# nse5310-module-stm32.net
KiCad netlist of a schematic drawn in Altium Designer
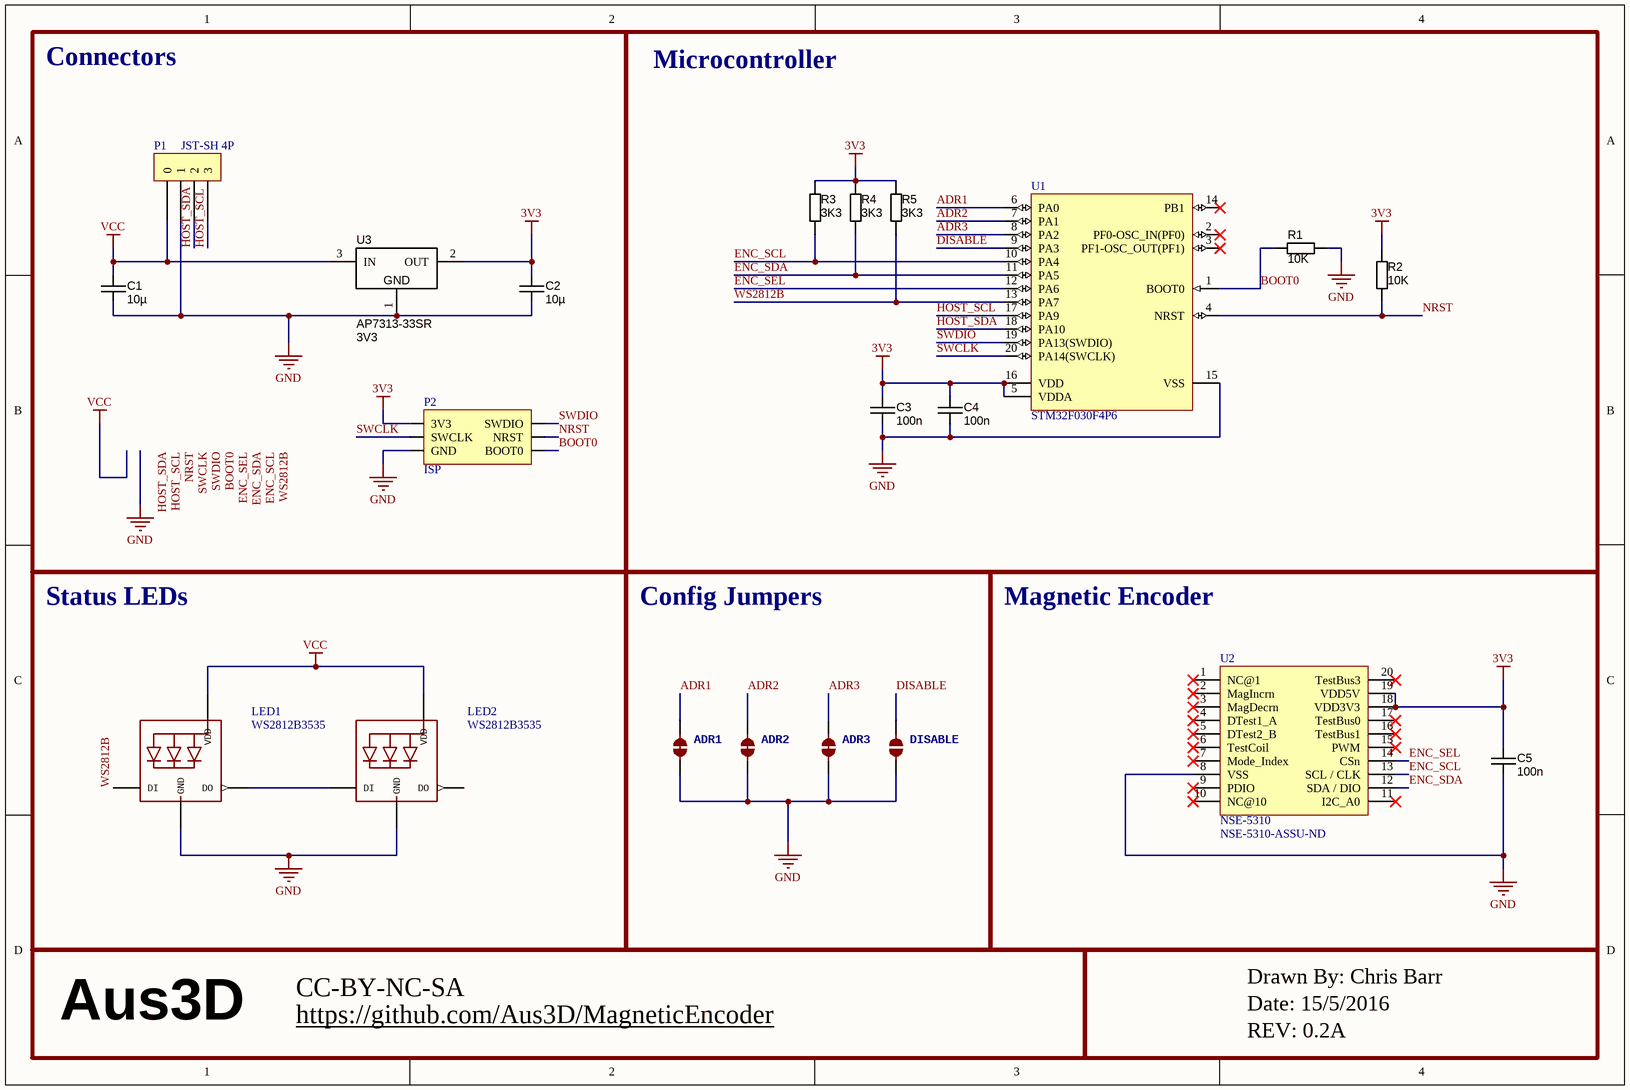
[diagram p0: nse5310-module-stm32.SchDoc]

(export (version "E")
  (design (tool "Eeschema 10.0.6"))
  (components
    (comp (ref "ADR1")
      (value "JUMPER-PAD-2-NC_BY_TRACE")
      (footprint "PAD-JUMPER-2-NC_BY_TRACE_YES_SILK")
      (libsource (lib "SparkFun-Passives") (part "JUMPER-PAD-2-NC_BY_TRACE"))
    )
    (comp (ref "ADR2")
      (value "JUMPER-PAD-2-NC_BY_TRACE")
      (footprint "PAD-JUMPER-2-NC_BY_TRACE_YES_SILK")
      (libsource (lib "SparkFun-Passives") (part "JUMPER-PAD-2-NC_BY_TRACE"))
    )
    (comp (ref "ADR3")
      (value "JUMPER-PAD-2-NC_BY_TRACE")
      (footprint "PAD-JUMPER-2-NC_BY_TRACE_YES_SILK")
      (libsource (lib "SparkFun-Passives") (part "JUMPER-PAD-2-NC_BY_TRACE"))
    )
    (comp (ref "C1")
      (value "10µ")
      (footprint "CAPC2012X135N")
      (description "Capacitor SMD Cer 10uF 10% 10V X5R 0805")
      (fields (field (name "TOLERANCE") "±10%") (field (name "Comment") "approved sub OK"))
      (libsource (lib "PBL - Capacitors") (part "CAPC_10u_0805_10V"))
    )
    (comp (ref "C2")
      (value "10µ")
      (footprint "CAPC2012X135N")
      (description "Capacitor SMD Cer 10uF 10% 10V X5R 0805")
      (fields (field (name "TOLERANCE") "±10%") (field (name "Comment") "approved sub OK"))
      (libsource (lib "PBL - Capacitors") (part "CAPC_10u_0805_10V"))
    )
    (comp (ref "C3")
      (value "100n")
      (footprint "CAPC1608X90N")
      (description "Capacitor SMD Cer 100nF 10% 50V X7R 0603")
      (fields (field (name "TOLERANCE") "±10%") (field (name "Comment") "approved sub OK"))
      (libsource (lib "PBL - Capacitors") (part "CAPC_100n_0603_X7R_50V_10%"))
    )
    (comp (ref "C4")
      (value "100n")
      (footprint "CAPC1608X90N")
      (description "Capacitor SMD Cer 100nF 10% 50V X7R 0603")
      (fields (field (name "TOLERANCE") "±10%") (field (name "Comment") "approved sub OK"))
      (libsource (lib "PBL - Capacitors") (part "CAPC_100n_0603_X7R_50V_10%"))
    )
    (comp (ref "C5")
      (value "100n")
      (footprint "CAPC1608X90N")
      (description "Capacitor SMD Cer 100nF 10% 50V X7R 0603")
      (fields (field (name "TOLERANCE") "±10%") (field (name "Comment") "approved sub OK"))
      (libsource (lib "PBL - Capacitors") (part "CAPC_100n_0603_X7R_50V_10%"))
    )
    (comp (ref "DISABLE")
      (value "JUMPER-PAD-2-NO")
      (footprint "PAD-JUMPER-2-NO_NO_SILK")
      (libsource (lib "SparkFun-Passives") (part "JUMPER-PAD-2-NO"))
    )
    (comp (ref "LED1")
      (value "WS2812B3535")
      (footprint "LED3535")
      (libsource (lib "adafruit") (part "WS2812B3535"))
    )
    (comp (ref "LED2")
      (value "WS2812B3535")
      (footprint "LED3535")
      (libsource (lib "adafruit") (part "WS2812B3535"))
    )
    (comp (ref "P1")
      (value "JST-SH 4P")
      (footprint "SM04B-SRSS-TB")
      (libsource (lib "Schlib1") (part "SM04B-SRSS-TB"))
    )
    (comp (ref "P2")
      (value "ISP")
      (footprint "ICSP Pads - SMD")
      (libsource (lib "Schlib1") (part "ISP Header"))
    )
    (comp (ref "R1")
      (value "10K")
      (footprint "RESC1608X55N")
      (description "Resistor SMD chip 10k Ohm 0.1W 5% 0603")
      (fields (field (name "TOLERANCE") "±5%") (field (name "Comment") "Thick Film"))
      (libsource (lib "PBL - Resistors") (part "RES_10K_0603_5%"))
    )
    (comp (ref "R2")
      (value "10K")
      (footprint "RESC1608X55N")
      (description "Resistor SMD chip 10k Ohm 0.1W 5% 0603")
      (fields (field (name "TOLERANCE") "±5%") (field (name "Comment") "Thick Film"))
      (libsource (lib "") (part "RES_10K_0603_5%_1"))
    )
    (comp (ref "R3")
      (value "3K3")
      (footprint "RESC1608X55N")
      (description "Resistor SMD chip 3.3k Ohm 0.1W 5% 0603")
      (fields (field (name "TOLERANCE") "±5%") (field (name "Comment") "Thick Film"))
      (libsource (lib "PBL - Resistors") (part "RES_3K3_0603_5%"))
    )
    (comp (ref "R4")
      (value "3K3")
      (footprint "RESC1608X55N")
      (description "Resistor SMD chip 3.3k Ohm 0.1W 5% 0603")
      (fields (field (name "TOLERANCE") "±5%") (field (name "Comment") "Thick Film"))
      (libsource (lib "PBL - Resistors") (part "RES_3K3_0603_5%"))
    )
    (comp (ref "R5")
      (value "3K3")
      (footprint "RESC1608X55N")
      (description "Resistor SMD chip 3.3k Ohm 0.1W 5% 0603")
      (fields (field (name "TOLERANCE") "±5%") (field (name "Comment") "Thick Film"))
      (libsource (lib "PBL - Resistors") (part "RES_3K3_0603_5%"))
    )
    (comp (ref "U1")
      (value "STM32F030F4P6")
      (footprint "STM-TSSOP20_N")
      (libsource (lib "STMicroelectronics STM32 F0") (part "STM32F030F4P6"))
    )
    (comp (ref "U2")
      (value "NSE-5310")
      (footprint "NSE-5310")
      (fields (field (name "SUPPLIER PART NUMBER 1") "NSE-5310-ASSU-ND"))
      (libsource (lib "Schlib1") (part "NSE-5310"))
    )
    (comp (ref "U3")
      (value "AP7313-33SR")
      (footprint "SOT23-3")
      (description "Voltage Regulator 3.3V LDO SOT23R-3 SMD")
      (fields (field (name "TOLERANCE") "±2%") (field (name "ALTIUM_VALUE") "3V3"))
      (libsource (lib "PBL - Regulators") (part "VREG_3V3_AP7313-33SR"))
    )
  )
  (nets
    (net (code "1") (name "/ADR1") (class "Default")
      (node (ref "ADR1") (pin "2") (pinfunction "2_2") (pintype "passive"))
      (node (ref "U1") (pin "6") (pinfunction "PA0_6") (pintype "bidirectional"))
    )
    (net (code "2") (name "/ADR2") (class "Default")
      (node (ref "ADR2") (pin "2") (pinfunction "2_2") (pintype "passive"))
      (node (ref "U1") (pin "7") (pinfunction "PA1_7") (pintype "bidirectional"))
    )
    (net (code "3") (name "/ADR3") (class "Default")
      (node (ref "ADR3") (pin "2") (pinfunction "2_2") (pintype "passive"))
      (node (ref "U1") (pin "8") (pinfunction "PA2_8") (pintype "bidirectional"))
    )
    (net (code "4") (name "/BOOT0") (class "Default")
      (node (ref "P2") (pin "5") (pinfunction "BOOT0_5") (pintype "passive"))
      (node (ref "R1") (pin "1") (pinfunction "1_1") (pintype "passive"))
      (node (ref "U1") (pin "1") (pinfunction "BOOT0_1") (pintype "input"))
    )
    (net (code "5") (name "/DISABLE") (class "Default")
      (node (ref "DISABLE") (pin "1") (pinfunction "1_1") (pintype "passive"))
      (node (ref "U1") (pin "9") (pinfunction "PA3_9") (pintype "bidirectional"))
    )
    (net (code "6") (name "/ENC_SCL") (class "Default")
      (node (ref "R3") (pin "2") (pinfunction "2_2") (pintype "passive"))
      (node (ref "U1") (pin "10") (pinfunction "PA4_10") (pintype "bidirectional"))
      (node (ref "U2") (pin "13") (pinfunction "SCL_/_CLK_13") (pintype "passive"))
    )
    (net (code "7") (name "/ENC_SDA") (class "Default")
      (node (ref "R4") (pin "2") (pinfunction "2_2") (pintype "passive"))
      (node (ref "U1") (pin "11") (pinfunction "PA5_11") (pintype "bidirectional"))
      (node (ref "U2") (pin "12") (pinfunction "SDA_/_DIO_12") (pintype "passive"))
    )
    (net (code "8") (name "/ENC_SEL") (class "Default")
      (node (ref "U1") (pin "12") (pinfunction "PA6_12") (pintype "bidirectional"))
      (node (ref "U2") (pin "14") (pinfunction "CSn_14") (pintype "passive"))
    )
    (net (code "9") (name "/HOST_SCL") (class "Default")
      (node (ref "P1") (pin "3") (pinfunction "3_3") (pintype "passive"))
      (node (ref "U1") (pin "17") (pinfunction "PA9_17") (pintype "bidirectional"))
    )
    (net (code "10") (name "/HOST_SDA") (class "Default")
      (node (ref "P1") (pin "2") (pinfunction "2_2") (pintype "passive"))
      (node (ref "U1") (pin "18") (pinfunction "PA10_18") (pintype "bidirectional"))
    )
    (net (code "11") (name "/NRST") (class "Default")
      (node (ref "P2") (pin "3") (pinfunction "NRST_3") (pintype "passive"))
      (node (ref "R2") (pin "1") (pinfunction "1_1") (pintype "passive"))
      (node (ref "U1") (pin "4") (pinfunction "NRST_4") (pintype "bidirectional"))
    )
    (net (code "12") (name "/SWCLK") (class "Default")
      (node (ref "P2") (pin "2") (pinfunction "SWCLK_2") (pintype "passive"))
      (node (ref "U1") (pin "20") (pinfunction "PA14(SWCLK)_20") (pintype "bidirectional"))
    )
    (net (code "13") (name "/SWDIO") (class "Default")
      (node (ref "P2") (pin "1") (pinfunction "SWDIO_1") (pintype "passive"))
      (node (ref "U1") (pin "19") (pinfunction "PA13(SWDIO)_19") (pintype "bidirectional"))
    )
    (net (code "14") (name "/WS2812B") (class "Default")
      (node (ref "LED1") (pin "1") (pinfunction "DI_1") (pintype "passive"))
      (node (ref "R5") (pin "2") (pinfunction "2_2") (pintype "passive"))
      (node (ref "U1") (pin "13") (pinfunction "PA7_13") (pintype "bidirectional"))
    )
    (net (code "15") (name "3V3") (class "Default")
      (node (ref "C2") (pin "1") (pintype "passive"))
      (node (ref "C3") (pin "1") (pintype "passive"))
      (node (ref "C4") (pin "1") (pintype "passive"))
      (node (ref "C5") (pin "1") (pintype "passive"))
      (node (ref "P2") (pin "0") (pinfunction "3V3_0") (pintype "passive"))
      (node (ref "R2") (pin "2") (pinfunction "2_2") (pintype "passive"))
      (node (ref "R3") (pin "1") (pinfunction "1_1") (pintype "passive"))
      (node (ref "R4") (pin "1") (pinfunction "1_1") (pintype "passive"))
      (node (ref "R5") (pin "1") (pinfunction "1_1") (pintype "passive"))
      (node (ref "U1") (pin "16") (pinfunction "VDD_16") (pintype "power_in"))
      (node (ref "U1") (pin "5") (pinfunction "VDDA_5") (pintype "power_in"))
      (node (ref "U2") (pin "18") (pinfunction "VDD3V3_18") (pintype "passive"))
      (node (ref "U2") (pin "19") (pinfunction "VDD5V_19") (pintype "passive"))
      (node (ref "U3") (pin "2") (pinfunction "OUT_2") (pintype "power_in"))
    )
    (net (code "16") (name "GND") (class "Default")
      (node (ref "ADR1") (pin "1") (pinfunction "1_1") (pintype "passive"))
      (node (ref "ADR2") (pin "1") (pinfunction "1_1") (pintype "passive"))
      (node (ref "ADR3") (pin "1") (pinfunction "1_1") (pintype "passive"))
      (node (ref "C1") (pin "2") (pintype "passive"))
      (node (ref "C2") (pin "2") (pintype "passive"))
      (node (ref "C3") (pin "2") (pintype "passive"))
      (node (ref "C4") (pin "2") (pintype "passive"))
      (node (ref "C5") (pin "2") (pintype "passive"))
      (node (ref "DISABLE") (pin "2") (pinfunction "2_2") (pintype "passive"))
      (node (ref "LED1") (pin "4") (pinfunction "GND_4") (pintype "power_in"))
      (node (ref "LED2") (pin "4") (pinfunction "GND_4") (pintype "power_in"))
      (node (ref "P1") (pin "1") (pinfunction "1_1") (pintype "passive"))
      (node (ref "P2") (pin "4") (pinfunction "GND_4") (pintype "passive"))
      (node (ref "R1") (pin "2") (pinfunction "2_2") (pintype "passive"))
      (node (ref "U1") (pin "15") (pinfunction "VSS_15") (pintype "power_in"))
      (node (ref "U2") (pin "8") (pinfunction "VSS_8") (pintype "passive"))
      (node (ref "U3") (pin "1") (pinfunction "GND_1") (pintype "power_in"))
    )
    (net (code "17") (name "Net-(LED1-DO)") (class "Default")
      (node (ref "LED1") (pin "3") (pinfunction "DO_3") (pintype "output"))
      (node (ref "LED2") (pin "1") (pinfunction "DI_1") (pintype "passive"))
    )
    (net (code "18") (name "VCC") (class "Default")
      (node (ref "C1") (pin "1") (pintype "passive"))
      (node (ref "LED1") (pin "2") (pinfunction "VDD_2") (pintype "power_in"))
      (node (ref "LED2") (pin "2") (pinfunction "VDD_2") (pintype "power_in"))
      (node (ref "P1") (pin "0") (pinfunction "0_0") (pintype "passive"))
      (node (ref "U3") (pin "3") (pinfunction "IN_3") (pintype "power_in"))
    )
    (net (code "19") (name "unconnected-(LED2-DO-Pad3)") (class "Default")
      (node (ref "LED2") (pin "3") (pinfunction "DO_3") (pintype "output"))
    )
    (net (code "20") (name "unconnected-(U1-PB1-Pad14)") (class "Default")
      (node (ref "U1") (pin "14") (pinfunction "PB1_14") (pintype "bidirectional+no_connect"))
    )
    (net (code "21") (name "unconnected-(U1-PF0-OSC_IN(PF0)-Pad2)") (class "Default")
      (node (ref "U1") (pin "2") (pinfunction "PF0-OSC_IN(PF0)_2") (pintype "bidirectional+no_connect"))
    )
    (net (code "22") (name "unconnected-(U1-PF1-OSC_OUT(PF1)-Pad3)") (class "Default")
      (node (ref "U1") (pin "3") (pinfunction "PF1-OSC_OUT(PF1)_3") (pintype "bidirectional+no_connect"))
    )
    (net (code "23") (name "unconnected-(U2-DTest1_A-Pad4)") (class "Default")
      (node (ref "U2") (pin "4") (pinfunction "DTest1_A_4") (pintype "passive+no_connect"))
    )
    (net (code "24") (name "unconnected-(U2-DTest2_B-Pad5)") (class "Default")
      (node (ref "U2") (pin "5") (pinfunction "DTest2_B_5") (pintype "passive+no_connect"))
    )
    (net (code "25") (name "unconnected-(U2-I2C_A0-Pad11)") (class "Default")
      (node (ref "U2") (pin "11") (pinfunction "I2C_A0_11") (pintype "passive+no_connect"))
    )
    (net (code "26") (name "unconnected-(U2-MagDecrn-Pad3)") (class "Default")
      (node (ref "U2") (pin "3") (pinfunction "MagDecrn_3") (pintype "passive+no_connect"))
    )
    (net (code "27") (name "unconnected-(U2-MagIncrn-Pad2)") (class "Default")
      (node (ref "U2") (pin "2") (pinfunction "MagIncrn_2") (pintype "passive+no_connect"))
    )
    (net (code "28") (name "unconnected-(U2-Mode_Index-Pad7)") (class "Default")
      (node (ref "U2") (pin "7") (pinfunction "Mode_Index_7") (pintype "passive+no_connect"))
    )
    (net (code "29") (name "unconnected-(U2-NC@1-Pad1)") (class "Default")
      (node (ref "U2") (pin "1") (pinfunction "NC@1_1") (pintype "passive+no_connect"))
    )
    (net (code "30") (name "unconnected-(U2-NC@10-Pad10)") (class "Default")
      (node (ref "U2") (pin "10") (pinfunction "NC@10_10") (pintype "passive+no_connect"))
    )
    (net (code "31") (name "unconnected-(U2-PDIO-Pad9)") (class "Default")
      (node (ref "U2") (pin "9") (pinfunction "PDIO_9") (pintype "passive+no_connect"))
    )
    (net (code "32") (name "unconnected-(U2-PWM-Pad15)") (class "Default")
      (node (ref "U2") (pin "15") (pinfunction "PWM_15") (pintype "passive+no_connect"))
    )
    (net (code "33") (name "unconnected-(U2-TestBus0-Pad17)") (class "Default")
      (node (ref "U2") (pin "17") (pinfunction "TestBus0_17") (pintype "passive+no_connect"))
    )
    (net (code "34") (name "unconnected-(U2-TestBus1-Pad16)") (class "Default")
      (node (ref "U2") (pin "16") (pinfunction "TestBus1_16") (pintype "passive+no_connect"))
    )
    (net (code "35") (name "unconnected-(U2-TestBus3-Pad20)") (class "Default")
      (node (ref "U2") (pin "20") (pinfunction "TestBus3_20") (pintype "passive+no_connect"))
    )
    (net (code "36") (name "unconnected-(U2-TestCoil-Pad6)") (class "Default")
      (node (ref "U2") (pin "6") (pinfunction "TestCoil_6") (pintype "passive+no_connect"))
    )
  )
)
